# 8_Outputs_Card_with_I2C_schematic.net
KiCad netlist of a schematic drawn in EasyEDA
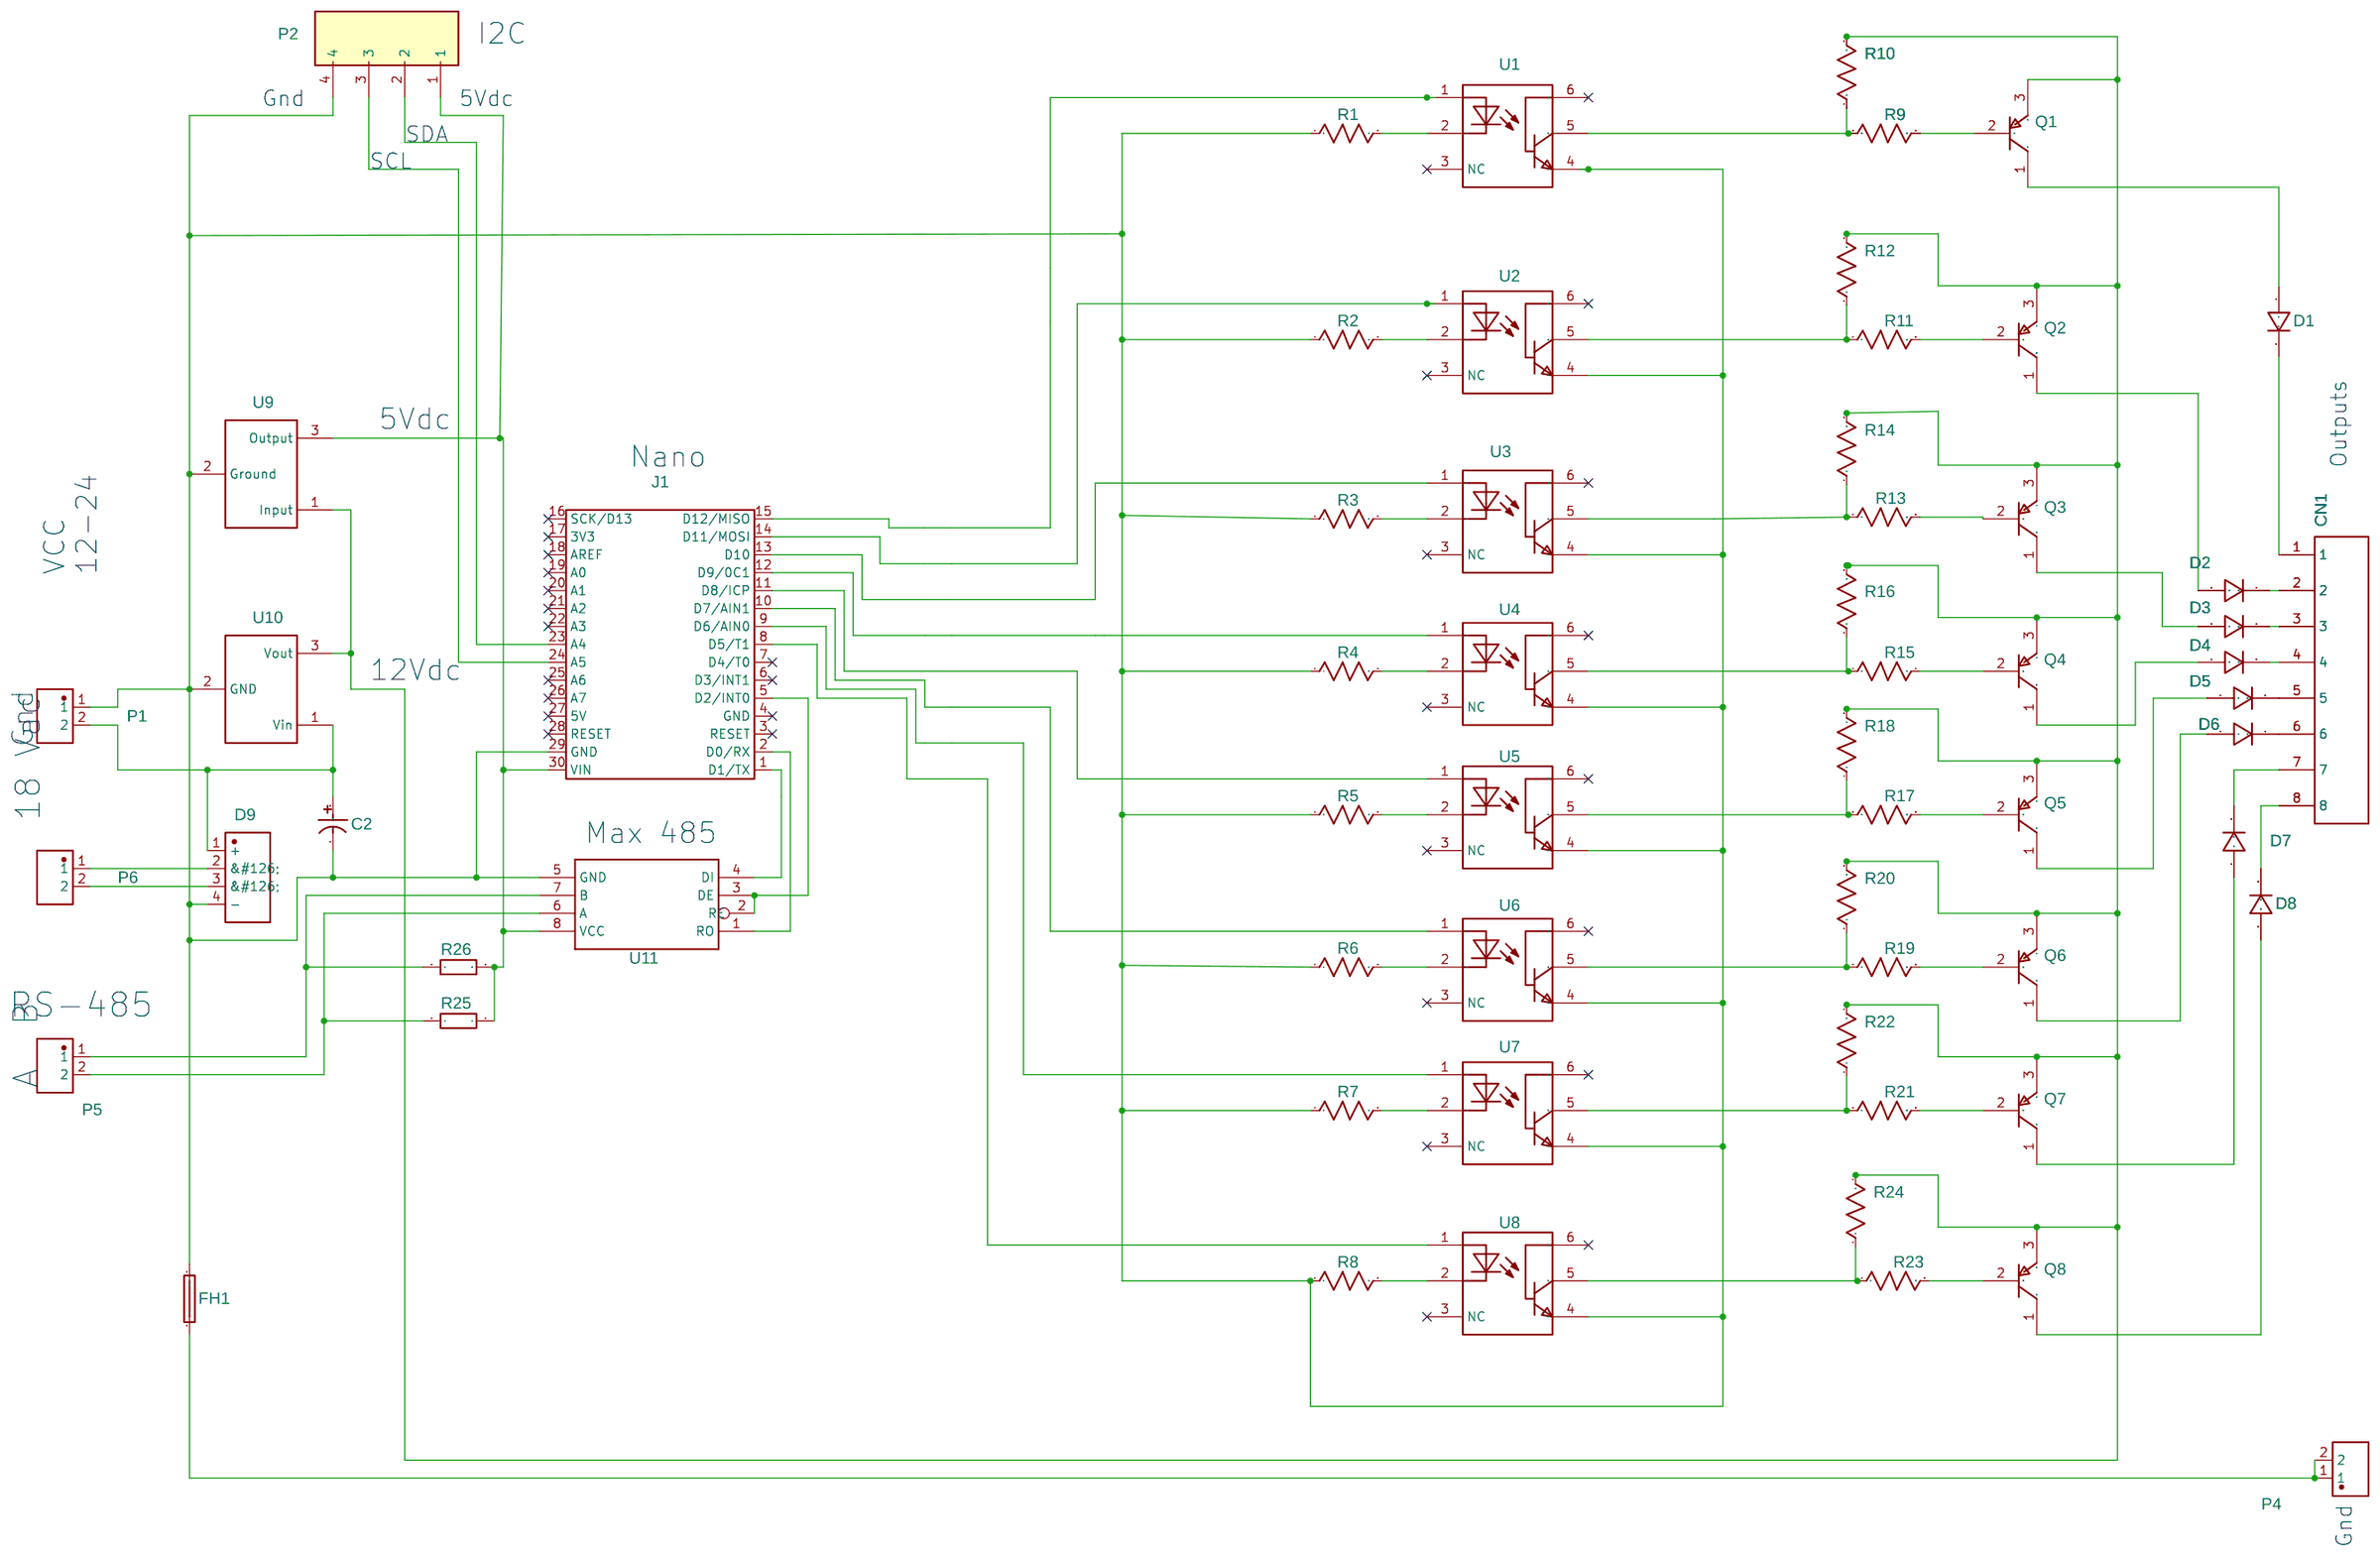
[diagram p0: schematic sheet]

(export (version "E")
  (design (tool "Eeschema 10.0.6"))
  (components
    (comp (ref "C2")
      (value "470uF")
      (fields
        (field (name "BOM_Manufacturer Part") "470uF 100V 16*25")
        (field (name "BOM_Supplier Part") "C72551")
      )
      (libsource (lib "") (part "470uF 100V 16*25"))
    )
    (comp (ref "CN1")
      (value "WJ25C-B-7.62-8P-13-00A")
      (fields (field (name "BOM_Supplier Part") "C49492"))
      (libsource (lib "") (part "Unknown_1530_395"))
    )
    (comp (ref "D1")
      (value "1N4001")
      (fields (field (name "BOM_Supplier Part") "C169150"))
      (libsource (lib "") (part "Unknown_1510_195"))
    )
    (comp (ref "D2")
      (value "1N4001")
      (fields (field (name "BOM_Supplier Part") "C169150"))
      (libsource (lib "") (part "Unknown_1485_345"))
    )
    (comp (ref "D3")
      (value "1N4001")
      (fields (field (name "BOM_Supplier Part") "C169150"))
      (libsource (lib "") (part "Unknown_1485_365"))
    )
    (comp (ref "D4")
      (value "1N4001")
      (fields (field (name "BOM_Supplier Part") "C169150"))
      (libsource (lib "") (part "Unknown_1485_385"))
    )
    (comp (ref "D5")
      (value "1N4001")
      (fields (field (name "BOM_Supplier Part") "C169150"))
      (libsource (lib "") (part "Unknown_1490_405"))
    )
    (comp (ref "D6")
      (value "1N4001")
      (fields (field (name "BOM_Supplier Part") "C169150"))
      (libsource (lib "") (part "Unknown_1490_425"))
    )
    (comp (ref "D7")
      (value "1N4001")
      (fields (field (name "BOM_Supplier Part") "C169150"))
      (libsource (lib "") (part "Unknown_1485_485"))
    )
    (comp (ref "D8")
      (value "1N4001")
      (fields (field (name "BOM_Supplier Part") "C169150"))
      (libsource (lib "") (part "Unknown_1500_520"))
    )
    (comp (ref "D9")
      (value "D50SB100")
      (fields (field (name "BOM_Supplier Part") "C411148"))
      (libsource (lib "") (part "Unknown_370_505"))
    )
    (comp (ref "FH1")
      (value "64600001003")
      (fields (field (name "BOM_Supplier Part") "C206887"))
      (libsource (lib "") (part "Unknown_345_740"))
    )
    (comp (ref "J1") (value "Arduino_Nano_Header") (libsource (lib "") (part "Unknown_605_375")))
    (comp (ref "P1")
      (value "WJ25C-B-2P")
      (fields (field (name "BOM_Supplier Part") "C8422"))
      (libsource (lib "") (part "Unknown_270_415"))
    )
    (comp (ref "P2")
      (value "WJ25C-B-4P")
      (fields (field (name "BOM_Supplier Part") "C8424"))
      (libsource (lib "") (part "WJ25C-B-4P"))
    )
    (comp (ref "P4")
      (value "WJ25C-B-2P")
      (fields (field (name "BOM_Supplier Part") "C8422"))
      (libsource (lib "") (part "Unknown_1550_835"))
    )
    (comp (ref "P5")
      (value "WJ25C-B-2P")
      (fields (field (name "BOM_Supplier Part") "C8422"))
      (libsource (lib "") (part "Unknown_270_610"))
    )
    (comp (ref "P6")
      (value "WJ25C-B-2P")
      (fields (field (name "BOM_Supplier Part") "C8422"))
      (libsource (lib "") (part "Unknown_270_505"))
    )
    (comp (ref "Q1")
      (value "2N4033")
      (fields (field (name "BOM_Supplier Part") "610-2N4033"))
      (libsource (lib "") (part "Unknown_1355_90"))
    )
    (comp (ref "Q2")
      (value "2N4033")
      (fields (field (name "BOM_Supplier Part") "610-2N4033"))
      (libsource (lib "") (part "Unknown_1360_205"))
    )
    (comp (ref "Q3")
      (value "2N4033")
      (fields (field (name "BOM_Supplier Part") "610-2N4033"))
      (libsource (lib "") (part "Unknown_1360_305"))
    )
    (comp (ref "Q4")
      (value "2N4033")
      (fields (field (name "BOM_Supplier Part") "610-2N4033"))
      (libsource (lib "") (part "Unknown_1360_390"))
    )
    (comp (ref "Q5")
      (value "2N4033")
      (fields (field (name "BOM_Supplier Part") "610-2N4033"))
      (libsource (lib "") (part "Unknown_1360_470"))
    )
    (comp (ref "Q6")
      (value "2N4033")
      (fields (field (name "BOM_Supplier Part") "610-2N4033"))
      (libsource (lib "") (part "Unknown_1360_555"))
    )
    (comp (ref "Q7")
      (value "2N4033")
      (fields (field (name "BOM_Supplier Part") "610-2N4033"))
      (libsource (lib "") (part "Unknown_1360_635"))
    )
    (comp (ref "Q8")
      (value "2N4033")
      (fields (field (name "BOM_Supplier Part") "610-2N4033"))
      (libsource (lib "") (part "Unknown_1360_730"))
    )
    (comp (ref "R1")
      (value "1k")
      (fields
        (field (name "BOM_Manufacturer Part") "MFR0W4F1001A50")
        (field (name "BOM_Supplier Part") "C57435")
      )
      (libsource (lib "") (part "Res_AXIAL-0.3(1/8W)_US"))
    )
    (comp (ref "R2")
      (value "1k")
      (fields
        (field (name "BOM_Manufacturer Part") "MFR0W4F1001A50")
        (field (name "BOM_Supplier Part") "C57435")
      )
      (libsource (lib "") (part "Res_AXIAL-0.3(1/8W)_US"))
    )
    (comp (ref "R3")
      (value "1k")
      (fields
        (field (name "BOM_Manufacturer Part") "MFR0W4F1001A50")
        (field (name "BOM_Supplier Part") "C57435")
      )
      (libsource (lib "") (part "Res_AXIAL-0.3(1/8W)_US"))
    )
    (comp (ref "R4")
      (value "1k")
      (fields
        (field (name "BOM_Manufacturer Part") "MFR0W4F1001A50")
        (field (name "BOM_Supplier Part") "C57435")
      )
      (libsource (lib "") (part "Res_AXIAL-0.3(1/8W)_US"))
    )
    (comp (ref "R5")
      (value "1k")
      (fields
        (field (name "BOM_Manufacturer Part") "MFR0W4F1001A50")
        (field (name "BOM_Supplier Part") "C57435")
      )
      (libsource (lib "") (part "Res_AXIAL-0.3(1/8W)_US"))
    )
    (comp (ref "R6")
      (value "1k")
      (fields
        (field (name "BOM_Manufacturer Part") "MFR0W4F1001A50")
        (field (name "BOM_Supplier Part") "C57435")
      )
      (libsource (lib "") (part "Res_AXIAL-0.3(1/8W)_US"))
    )
    (comp (ref "R7")
      (value "1k")
      (fields
        (field (name "BOM_Manufacturer Part") "MFR0W4F1001A50")
        (field (name "BOM_Supplier Part") "C57435")
      )
      (libsource (lib "") (part "Res_AXIAL-0.3(1/8W)_US"))
    )
    (comp (ref "R8")
      (value "1k")
      (fields
        (field (name "BOM_Manufacturer Part") "MFR0W4F1001A50")
        (field (name "BOM_Supplier Part") "C57435")
      )
      (libsource (lib "") (part "Res_AXIAL-0.3(1/8W)_US"))
    )
    (comp (ref "R9")
      (value "1k")
      (fields
        (field (name "BOM_Manufacturer Part") "MFR0W4F1001A50")
        (field (name "BOM_Supplier Part") "C57435")
      )
      (libsource (lib "") (part "Res_AXIAL-0.3(1/8W)_US"))
    )
    (comp (ref "R10")
      (value "1k")
      (fields
        (field (name "BOM_Manufacturer Part") "MFR0W4F1001A50")
        (field (name "BOM_Supplier Part") "C57435")
      )
      (libsource (lib "") (part "Res_AXIAL-0.3(1/8W)_US_1"))
    )
    (comp (ref "R11")
      (value "1k")
      (fields
        (field (name "BOM_Manufacturer Part") "MFR0W4F1001A50")
        (field (name "BOM_Supplier Part") "C57435")
      )
      (libsource (lib "") (part "Res_AXIAL-0.3(1/8W)_US"))
    )
    (comp (ref "R12")
      (value "1k")
      (fields
        (field (name "BOM_Manufacturer Part") "MFR0W4F1001A50")
        (field (name "BOM_Supplier Part") "C57435")
      )
      (libsource (lib "") (part "Res_AXIAL-0.3(1/8W)_US_1"))
    )
    (comp (ref "R13")
      (value "1k")
      (fields
        (field (name "BOM_Manufacturer Part") "MFR0W4F1001A50")
        (field (name "BOM_Supplier Part") "C57435")
      )
      (libsource (lib "") (part "Res_AXIAL-0.3(1/8W)_US"))
    )
    (comp (ref "R14")
      (value "1k")
      (fields
        (field (name "BOM_Manufacturer Part") "MFR0W4F1001A50")
        (field (name "BOM_Supplier Part") "C57435")
      )
      (libsource (lib "") (part "Res_AXIAL-0.3(1/8W)_US_1"))
    )
    (comp (ref "R15")
      (value "1k")
      (fields
        (field (name "BOM_Manufacturer Part") "MFR0W4F1001A50")
        (field (name "BOM_Supplier Part") "C57435")
      )
      (libsource (lib "") (part "Res_AXIAL-0.3(1/8W)_US"))
    )
    (comp (ref "R16")
      (value "1k")
      (fields
        (field (name "BOM_Manufacturer Part") "MFR0W4F1001A50")
        (field (name "BOM_Supplier Part") "C57435")
      )
      (libsource (lib "") (part "Res_AXIAL-0.3(1/8W)_US_1"))
    )
    (comp (ref "R17")
      (value "1k")
      (fields
        (field (name "BOM_Manufacturer Part") "MFR0W4F1001A50")
        (field (name "BOM_Supplier Part") "C57435")
      )
      (libsource (lib "") (part "Res_AXIAL-0.3(1/8W)_US"))
    )
    (comp (ref "R18")
      (value "1k")
      (fields
        (field (name "BOM_Manufacturer Part") "MFR0W4F1001A50")
        (field (name "BOM_Supplier Part") "C57435")
      )
      (libsource (lib "") (part "Res_AXIAL-0.3(1/8W)_US_1"))
    )
    (comp (ref "R19")
      (value "1k")
      (fields
        (field (name "BOM_Manufacturer Part") "MFR0W4F1001A50")
        (field (name "BOM_Supplier Part") "C57435")
      )
      (libsource (lib "") (part "Res_AXIAL-0.3(1/8W)_US"))
    )
    (comp (ref "R20")
      (value "1k")
      (fields
        (field (name "BOM_Manufacturer Part") "MFR0W4F1001A50")
        (field (name "BOM_Supplier Part") "C57435")
      )
      (libsource (lib "") (part "Res_AXIAL-0.3(1/8W)_US_1"))
    )
    (comp (ref "R21")
      (value "1k")
      (fields
        (field (name "BOM_Manufacturer Part") "MFR0W4F1001A50")
        (field (name "BOM_Supplier Part") "C57435")
      )
      (libsource (lib "") (part "Res_AXIAL-0.3(1/8W)_US"))
    )
    (comp (ref "R22")
      (value "1k")
      (fields
        (field (name "BOM_Manufacturer Part") "MFR0W4F1001A50")
        (field (name "BOM_Supplier Part") "C57435")
      )
      (libsource (lib "") (part "Res_AXIAL-0.3(1/8W)_US_1"))
    )
    (comp (ref "R23")
      (value "1k")
      (fields
        (field (name "BOM_Manufacturer Part") "MFR0W4F1001A50")
        (field (name "BOM_Supplier Part") "C57435")
      )
      (libsource (lib "") (part "Res_AXIAL-0.3(1/8W)_US"))
    )
    (comp (ref "R24")
      (value "1k")
      (fields
        (field (name "BOM_Manufacturer Part") "MFR0W4F1001A50")
        (field (name "BOM_Supplier Part") "C57435")
      )
      (libsource (lib "") (part "Res_AXIAL-0.3(1/8W)_US_1"))
    )
    (comp (ref "R25")
      (value "10K")
      (fields
        (field (name "BOM_Manufacturer Part") "CFR0W4J0103A50")
        (field (name "BOM_Supplier Part") "C61299")
      )
      (libsource (lib "") (part "CFR0W4J0103A50"))
    )
    (comp (ref "R26")
      (value "10K")
      (fields
        (field (name "BOM_Manufacturer Part") "CFR0W4J0103A50")
        (field (name "BOM_Supplier Part") "C61299")
      )
      (libsource (lib "") (part "CFR0W4J0103A50"))
    )
    (comp (ref "U1")
      (value "4N25M")
      (fields (field (name "BOM_Supplier Part") "C5241"))
      (libsource (lib "") (part "Unknown_1080_90"))
    )
    (comp (ref "U2")
      (value "4N25M")
      (fields (field (name "BOM_Supplier Part") "C5241"))
      (libsource (lib "") (part "Unknown_1080_205"))
    )
    (comp (ref "U3")
      (value "4N25M")
      (fields (field (name "BOM_Supplier Part") "C5241"))
      (libsource (lib "") (part "Unknown_1080_305"))
    )
    (comp (ref "U4")
      (value "4N25M")
      (fields (field (name "BOM_Supplier Part") "C5241"))
      (libsource (lib "") (part "Unknown_1080_390"))
    )
    (comp (ref "U5")
      (value "4N25M")
      (fields (field (name "BOM_Supplier Part") "C5241"))
      (libsource (lib "") (part "Unknown_1080_470"))
    )
    (comp (ref "U6")
      (value "4N25M")
      (fields (field (name "BOM_Supplier Part") "C5241"))
      (libsource (lib "") (part "Unknown_1080_555"))
    )
    (comp (ref "U7")
      (value "4N25M")
      (fields (field (name "BOM_Supplier Part") "C5241"))
      (libsource (lib "") (part "Unknown_1080_635"))
    )
    (comp (ref "U8")
      (value "4N25M")
      (fields (field (name "BOM_Supplier Part") "C5241"))
      (libsource (lib "") (part "Unknown_1080_730"))
    )
    (comp (ref "U9")
      (value "MC7805BTG")
      (fields (field (name "BOM_Supplier Part") "C45385"))
      (libsource (lib "") (part "Unknown_385_280"))
    )
    (comp (ref "U10")
      (value "CJ7812")
      (fields (field (name "BOM_Supplier Part") "C77894"))
      (libsource (lib "") (part "Unknown_385_400"))
    )
    (comp (ref "U11") (value "MAX485DIL") (libsource (lib "") (part "Unknown_600_520")))
  )
  (nets
    (net (code "1") (name "Net-(CN1-Pad1)") (class "Default")
      (node (ref "CN1") (pin "1") (pinfunction "1_1") (pintype "input"))
      (node (ref "D1") (pin "2") (pinfunction "2_2") (pintype "unspecified"))
    )
    (net (code "2") (name "Net-(CN1-Pad2)") (class "Default")
      (node (ref "CN1") (pin "2") (pinfunction "2_2") (pintype "input"))
      (node (ref "D2") (pin "2") (pinfunction "2_2") (pintype "unspecified"))
    )
    (net (code "3") (name "Net-(CN1-Pad3)") (class "Default")
      (node (ref "CN1") (pin "3") (pinfunction "3_3") (pintype "input"))
      (node (ref "D3") (pin "2") (pinfunction "2_2") (pintype "unspecified"))
    )
    (net (code "4") (name "Net-(CN1-Pad4)") (class "Default")
      (node (ref "CN1") (pin "4") (pinfunction "4_4") (pintype "input"))
      (node (ref "D4") (pin "2") (pinfunction "2_2") (pintype "unspecified"))
    )
    (net (code "5") (name "Net-(CN1-Pad5)") (class "Default")
      (node (ref "CN1") (pin "5") (pinfunction "5_5") (pintype "input"))
      (node (ref "D5") (pin "2") (pinfunction "2_2") (pintype "unspecified"))
    )
    (net (code "6") (name "Net-(CN1-Pad6)") (class "Default")
      (node (ref "CN1") (pin "6") (pinfunction "6_6") (pintype "input"))
      (node (ref "D6") (pin "2") (pinfunction "2_2") (pintype "unspecified"))
    )
    (net (code "7") (name "Net-(CN1-Pad7)") (class "Default")
      (node (ref "CN1") (pin "7") (pinfunction "7_7") (pintype "input"))
      (node (ref "D7") (pin "2") (pinfunction "2_2") (pintype "unspecified"))
    )
    (net (code "8") (name "Net-(CN1-Pad8)") (class "Default")
      (node (ref "CN1") (pin "8") (pinfunction "8_8") (pintype "input"))
      (node (ref "D8") (pin "2") (pinfunction "2_2") (pintype "unspecified"))
    )
    (net (code "9") (name "Net-(D9-&#126;-Pad2)") (class "Default")
      (node (ref "D9") (pin "2") (pinfunction "&#126;_2") (pintype "unspecified"))
      (node (ref "P6") (pin "1") (pinfunction "1_1") (pintype "unspecified"))
    )
    (net (code "10") (name "Net-(D9-&#126;-Pad3)") (class "Default")
      (node (ref "D9") (pin "3") (pinfunction "&#126;_3") (pintype "unspecified"))
      (node (ref "P6") (pin "2") (pinfunction "2_2") (pintype "unspecified"))
    )
    (net (code "11") (name "Net-(D9-+)") (class "Default")
      (node (ref "C2") (pin "1") (pinfunction "1_1") (pintype "input"))
      (node (ref "D9") (pin "1") (pinfunction "+_1") (pintype "unspecified"))
      (node (ref "P1") (pin "2") (pinfunction "2_2") (pintype "unspecified"))
      (node (ref "U10") (pin "1") (pinfunction "Vin_1") (pintype "unspecified"))
    )
    (net (code "12") (name "Net-(D9--)") (class "Default")
      (node (ref "C2") (pin "2") (pinfunction "2_2") (pintype "input"))
      (node (ref "D9") (pin "4") (pinfunction "-_4") (pintype "unspecified"))
      (node (ref "FH1") (pin "2") (pinfunction "2_2") (pintype "unspecified"))
      (node (ref "J1") (pin "29") (pinfunction "GND_29") (pintype "unspecified"))
      (node (ref "P1") (pin "1") (pinfunction "1_1") (pintype "unspecified"))
      (node (ref "P2") (pin "4") (pinfunction "4_4") (pintype "input"))
      (node (ref "R1") (pin "1") (pinfunction "1_1") (pintype "unspecified"))
      (node (ref "R2") (pin "1") (pinfunction "1_1") (pintype "unspecified"))
      (node (ref "R3") (pin "1") (pinfunction "1_1") (pintype "unspecified"))
      (node (ref "R4") (pin "1") (pinfunction "1_1") (pintype "unspecified"))
      (node (ref "R5") (pin "1") (pinfunction "1_1") (pintype "unspecified"))
      (node (ref "R6") (pin "1") (pinfunction "1_1") (pintype "unspecified"))
      (node (ref "R7") (pin "1") (pinfunction "1_1") (pintype "unspecified"))
      (node (ref "R8") (pin "1") (pinfunction "1_1") (pintype "unspecified"))
      (node (ref "U1") (pin "4") (pinfunction "4_4") (pintype "unspecified"))
      (node (ref "U10") (pin "2") (pinfunction "GND_2") (pintype "unspecified"))
      (node (ref "U11") (pin "5") (pinfunction "GND_5") (pintype "unspecified"))
      (node (ref "U2") (pin "4") (pinfunction "4_4") (pintype "unspecified"))
      (node (ref "U3") (pin "4") (pinfunction "4_4") (pintype "unspecified"))
      (node (ref "U4") (pin "4") (pinfunction "4_4") (pintype "unspecified"))
      (node (ref "U5") (pin "4") (pinfunction "4_4") (pintype "unspecified"))
      (node (ref "U6") (pin "4") (pinfunction "4_4") (pintype "unspecified"))
      (node (ref "U7") (pin "4") (pinfunction "4_4") (pintype "unspecified"))
      (node (ref "U8") (pin "4") (pinfunction "4_4") (pintype "unspecified"))
      (node (ref "U9") (pin "2") (pinfunction "Ground_2") (pintype "unspecified"))
    )
    (net (code "13") (name "Net-(FH1-Pad1)") (class "Default")
      (node (ref "FH1") (pin "1") (pinfunction "1_1") (pintype "unspecified"))
      (node (ref "P4") (pin "1") (pinfunction "1_1") (pintype "unspecified"))
      (node (ref "P4") (pin "2") (pinfunction "2_2") (pintype "unspecified"))
    )
    (net (code "14") (name "Net-(J1-A4)") (class "Default")
      (node (ref "J1") (pin "23") (pinfunction "A4_23") (pintype "unspecified"))
      (node (ref "P2") (pin "2") (pinfunction "2_2") (pintype "input"))
    )
    (net (code "15") (name "Net-(J1-A5)") (class "Default")
      (node (ref "J1") (pin "24") (pinfunction "A5_24") (pintype "unspecified"))
      (node (ref "P2") (pin "3") (pinfunction "3_3") (pintype "input"))
    )
    (net (code "16") (name "Net-(J1-D0{slash}RX)") (class "Default")
      (node (ref "J1") (pin "2") (pinfunction "D0/RX_2") (pintype "unspecified"))
      (node (ref "U11") (pin "1") (pinfunction "RO_1") (pintype "unspecified"))
    )
    (net (code "17") (name "Net-(J1-D1{slash}TX)") (class "Default")
      (node (ref "J1") (pin "1") (pinfunction "D1/TX_1") (pintype "unspecified"))
      (node (ref "U11") (pin "4") (pinfunction "DI_4") (pintype "unspecified"))
    )
    (net (code "18") (name "Net-(J1-D2{slash}INT0)") (class "Default")
      (node (ref "J1") (pin "5") (pinfunction "D2/INT0_5") (pintype "unspecified"))
      (node (ref "U11") (pin "2") (pinfunction "RE_2") (pintype "unspecified"))
      (node (ref "U11") (pin "3") (pinfunction "DE_3") (pintype "unspecified"))
    )
    (net (code "19") (name "Net-(J1-D5{slash}T1)") (class "Default")
      (node (ref "J1") (pin "8") (pinfunction "D5/T1_8") (pintype "unspecified"))
      (node (ref "U8") (pin "1") (pinfunction "1_1") (pintype "unspecified"))
    )
    (net (code "20") (name "Net-(J1-D6{slash}AIN0)") (class "Default")
      (node (ref "J1") (pin "9") (pinfunction "D6/AIN0_9") (pintype "unspecified"))
      (node (ref "U7") (pin "1") (pinfunction "1_1") (pintype "unspecified"))
    )
    (net (code "21") (name "Net-(J1-D7{slash}AIN1)") (class "Default")
      (node (ref "J1") (pin "10") (pinfunction "D7/AIN1_10") (pintype "unspecified"))
      (node (ref "U6") (pin "1") (pinfunction "1_1") (pintype "unspecified"))
    )
    (net (code "22") (name "Net-(J1-D8{slash}ICP)") (class "Default")
      (node (ref "J1") (pin "11") (pinfunction "D8/ICP_11") (pintype "unspecified"))
      (node (ref "U5") (pin "1") (pinfunction "1_1") (pintype "unspecified"))
    )
    (net (code "23") (name "Net-(J1-D9{slash}0C1)") (class "Default")
      (node (ref "J1") (pin "12") (pinfunction "D9/0C1_12") (pintype "unspecified"))
      (node (ref "U4") (pin "1") (pinfunction "1_1") (pintype "unspecified"))
    )
    (net (code "24") (name "Net-(J1-D10)") (class "Default")
      (node (ref "J1") (pin "13") (pinfunction "D10_13") (pintype "unspecified"))
      (node (ref "U3") (pin "1") (pinfunction "1_1") (pintype "unspecified"))
    )
    (net (code "25") (name "Net-(J1-D11{slash}MOSI)") (class "Default")
      (node (ref "J1") (pin "14") (pinfunction "D11/MOSI_14") (pintype "unspecified"))
      (node (ref "U2") (pin "1") (pinfunction "1_1") (pintype "unspecified"))
    )
    (net (code "26") (name "Net-(J1-D12{slash}MISO)") (class "Default")
      (node (ref "J1") (pin "15") (pinfunction "D12/MISO_15") (pintype "unspecified"))
      (node (ref "U1") (pin "1") (pinfunction "1_1") (pintype "unspecified"))
    )
    (net (code "27") (name "Net-(J1-VIN)") (class "Default")
      (node (ref "J1") (pin "30") (pinfunction "VIN_30") (pintype "unspecified"))
      (node (ref "P2") (pin "1") (pinfunction "1_1") (pintype "input"))
      (node (ref "R25") (pin "2") (pinfunction "2_2") (pintype "input"))
      (node (ref "R26") (pin "2") (pinfunction "2_2") (pintype "input"))
      (node (ref "U11") (pin "8") (pinfunction "VCC_8") (pintype "unspecified"))
      (node (ref "U9") (pin "3") (pinfunction "Output_3") (pintype "unspecified"))
    )
    (net (code "28") (name "Net-(Q1-B)") (class "Default")
      (node (ref "Q1") (pin "2") (pinfunction "B_2") (pintype "unspecified"))
      (node (ref "R9") (pin "2") (pinfunction "2_2") (pintype "unspecified"))
    )
    (net (code "29") (name "Net-(Q1-C)") (class "Default")
      (node (ref "D1") (pin "1") (pinfunction "1_1") (pintype "unspecified"))
      (node (ref "Q1") (pin "1") (pinfunction "C_1") (pintype "unspecified"))
    )
    (net (code "30") (name "Net-(Q1-E)") (class "Default")
      (node (ref "Q1") (pin "3") (pinfunction "E_3") (pintype "unspecified"))
      (node (ref "Q2") (pin "3") (pinfunction "E_3") (pintype "unspecified"))
      (node (ref "Q3") (pin "3") (pinfunction "E_3") (pintype "unspecified"))
      (node (ref "Q4") (pin "3") (pinfunction "E_3") (pintype "unspecified"))
      (node (ref "Q5") (pin "3") (pinfunction "E_3") (pintype "unspecified"))
      (node (ref "Q6") (pin "3") (pinfunction "E_3") (pintype "unspecified"))
      (node (ref "Q7") (pin "3") (pinfunction "E_3") (pintype "unspecified"))
      (node (ref "Q8") (pin "3") (pinfunction "E_3") (pintype "unspecified"))
      (node (ref "R10") (pin "2") (pinfunction "2_2") (pintype "unspecified"))
      (node (ref "R12") (pin "2") (pinfunction "2_2") (pintype "unspecified"))
      (node (ref "R14") (pin "2") (pinfunction "2_2") (pintype "unspecified"))
      (node (ref "R16") (pin "2") (pinfunction "2_2") (pintype "unspecified"))
      (node (ref "R18") (pin "2") (pinfunction "2_2") (pintype "unspecified"))
      (node (ref "R20") (pin "2") (pinfunction "2_2") (pintype "unspecified"))
      (node (ref "R22") (pin "2") (pinfunction "2_2") (pintype "unspecified"))
      (node (ref "R24") (pin "2") (pinfunction "2_2") (pintype "unspecified"))
      (node (ref "U10") (pin "3") (pinfunction "Vout_3") (pintype "unspecified"))
      (node (ref "U9") (pin "1") (pinfunction "Input_1") (pintype "unspecified"))
    )
    (net (code "31") (name "Net-(Q2-B)") (class "Default")
      (node (ref "Q2") (pin "2") (pinfunction "B_2") (pintype "unspecified"))
      (node (ref "R11") (pin "2") (pinfunction "2_2") (pintype "unspecified"))
    )
    (net (code "32") (name "Net-(Q2-C)") (class "Default")
      (node (ref "D2") (pin "1") (pinfunction "1_1") (pintype "unspecified"))
      (node (ref "Q2") (pin "1") (pinfunction "C_1") (pintype "unspecified"))
    )
    (net (code "33") (name "Net-(Q3-B)") (class "Default")
      (node (ref "Q3") (pin "2") (pinfunction "B_2") (pintype "unspecified"))
      (node (ref "R13") (pin "2") (pinfunction "2_2") (pintype "unspecified"))
    )
    (net (code "34") (name "Net-(Q3-C)") (class "Default")
      (node (ref "D3") (pin "1") (pinfunction "1_1") (pintype "unspecified"))
      (node (ref "Q3") (pin "1") (pinfunction "C_1") (pintype "unspecified"))
    )
    (net (code "35") (name "Net-(Q4-B)") (class "Default")
      (node (ref "Q4") (pin "2") (pinfunction "B_2") (pintype "unspecified"))
      (node (ref "R15") (pin "2") (pinfunction "2_2") (pintype "unspecified"))
    )
    (net (code "36") (name "Net-(Q4-C)") (class "Default")
      (node (ref "D4") (pin "1") (pinfunction "1_1") (pintype "unspecified"))
      (node (ref "Q4") (pin "1") (pinfunction "C_1") (pintype "unspecified"))
    )
    (net (code "37") (name "Net-(Q5-B)") (class "Default")
      (node (ref "Q5") (pin "2") (pinfunction "B_2") (pintype "unspecified"))
      (node (ref "R17") (pin "2") (pinfunction "2_2") (pintype "unspecified"))
    )
    (net (code "38") (name "Net-(Q5-C)") (class "Default")
      (node (ref "D5") (pin "1") (pinfunction "1_1") (pintype "unspecified"))
      (node (ref "Q5") (pin "1") (pinfunction "C_1") (pintype "unspecified"))
    )
    (net (code "39") (name "Net-(Q6-B)") (class "Default")
      (node (ref "Q6") (pin "2") (pinfunction "B_2") (pintype "unspecified"))
      (node (ref "R19") (pin "2") (pinfunction "2_2") (pintype "unspecified"))
    )
    (net (code "40") (name "Net-(Q6-C)") (class "Default")
      (node (ref "D6") (pin "1") (pinfunction "1_1") (pintype "unspecified"))
      (node (ref "Q6") (pin "1") (pinfunction "C_1") (pintype "unspecified"))
    )
    (net (code "41") (name "Net-(Q7-B)") (class "Default")
      (node (ref "Q7") (pin "2") (pinfunction "B_2") (pintype "unspecified"))
      (node (ref "R21") (pin "2") (pinfunction "2_2") (pintype "unspecified"))
    )
    (net (code "42") (name "Net-(Q7-C)") (class "Default")
      (node (ref "D7") (pin "1") (pinfunction "1_1") (pintype "unspecified"))
      (node (ref "Q7") (pin "1") (pinfunction "C_1") (pintype "unspecified"))
    )
    (net (code "43") (name "Net-(Q8-B)") (class "Default")
      (node (ref "Q8") (pin "2") (pinfunction "B_2") (pintype "unspecified"))
      (node (ref "R23") (pin "2") (pinfunction "2_2") (pintype "unspecified"))
    )
    (net (code "44") (name "Net-(Q8-C)") (class "Default")
      (node (ref "D8") (pin "1") (pinfunction "1_1") (pintype "unspecified"))
      (node (ref "Q8") (pin "1") (pinfunction "C_1") (pintype "unspecified"))
    )
    (net (code "45") (name "Net-(R1-Pad2)") (class "Default")
      (node (ref "R1") (pin "2") (pinfunction "2_2") (pintype "unspecified"))
      (node (ref "U1") (pin "2") (pinfunction "2_2") (pintype "unspecified"))
    )
    (net (code "46") (name "Net-(R2-Pad2)") (class "Default")
      (node (ref "R2") (pin "2") (pinfunction "2_2") (pintype "unspecified"))
      (node (ref "U2") (pin "2") (pinfunction "2_2") (pintype "unspecified"))
    )
    (net (code "47") (name "Net-(R3-Pad2)") (class "Default")
      (node (ref "R3") (pin "2") (pinfunction "2_2") (pintype "unspecified"))
      (node (ref "U3") (pin "2") (pinfunction "2_2") (pintype "unspecified"))
    )
    (net (code "48") (name "Net-(R4-Pad2)") (class "Default")
      (node (ref "R4") (pin "2") (pinfunction "2_2") (pintype "unspecified"))
      (node (ref "U4") (pin "2") (pinfunction "2_2") (pintype "unspecified"))
    )
    (net (code "49") (name "Net-(R5-Pad2)") (class "Default")
      (node (ref "R5") (pin "2") (pinfunction "2_2") (pintype "unspecified"))
      (node (ref "U5") (pin "2") (pinfunction "2_2") (pintype "unspecified"))
    )
    (net (code "50") (name "Net-(R6-Pad2)") (class "Default")
      (node (ref "R6") (pin "2") (pinfunction "2_2") (pintype "unspecified"))
      (node (ref "U6") (pin "2") (pinfunction "2_2") (pintype "unspecified"))
    )
    (net (code "51") (name "Net-(R7-Pad2)") (class "Default")
      (node (ref "R7") (pin "2") (pinfunction "2_2") (pintype "unspecified"))
      (node (ref "U7") (pin "2") (pinfunction "2_2") (pintype "unspecified"))
    )
    (net (code "52") (name "Net-(R8-Pad2)") (class "Default")
      (node (ref "R8") (pin "2") (pinfunction "2_2") (pintype "unspecified"))
      (node (ref "U8") (pin "2") (pinfunction "2_2") (pintype "unspecified"))
    )
    (net (code "53") (name "Net-(R10-Pad1)") (class "Default")
      (node (ref "R10") (pin "1") (pinfunction "1_1") (pintype "unspecified"))
      (node (ref "R9") (pin "1") (pinfunction "1_1") (pintype "unspecified"))
      (node (ref "U1") (pin "5") (pinfunction "5_5") (pintype "unspecified"))
    )
    (net (code "54") (name "Net-(R11-Pad1)") (class "Default")
      (node (ref "R11") (pin "1") (pinfunction "1_1") (pintype "unspecified"))
      (node (ref "R12") (pin "1") (pinfunction "1_1") (pintype "unspecified"))
      (node (ref "U2") (pin "5") (pinfunction "5_5") (pintype "unspecified"))
    )
    (net (code "55") (name "Net-(R13-Pad1)") (class "Default")
      (node (ref "R13") (pin "1") (pinfunction "1_1") (pintype "unspecified"))
      (node (ref "R14") (pin "1") (pinfunction "1_1") (pintype "unspecified"))
      (node (ref "U3") (pin "5") (pinfunction "5_5") (pintype "unspecified"))
    )
    (net (code "56") (name "Net-(R15-Pad1)") (class "Default")
      (node (ref "R15") (pin "1") (pinfunction "1_1") (pintype "unspecified"))
      (node (ref "R16") (pin "1") (pinfunction "1_1") (pintype "unspecified"))
      (node (ref "U4") (pin "5") (pinfunction "5_5") (pintype "unspecified"))
    )
    (net (code "57") (name "Net-(R17-Pad1)") (class "Default")
      (node (ref "R17") (pin "1") (pinfunction "1_1") (pintype "unspecified"))
      (node (ref "R18") (pin "1") (pinfunction "1_1") (pintype "unspecified"))
      (node (ref "U5") (pin "5") (pinfunction "5_5") (pintype "unspecified"))
    )
    (net (code "58") (name "Net-(R19-Pad1)") (class "Default")
      (node (ref "R19") (pin "1") (pinfunction "1_1") (pintype "unspecified"))
      (node (ref "R20") (pin "1") (pinfunction "1_1") (pintype "unspecified"))
      (node (ref "U6") (pin "5") (pinfunction "5_5") (pintype "unspecified"))
    )
    (net (code "59") (name "Net-(R21-Pad1)") (class "Default")
      (node (ref "R21") (pin "1") (pinfunction "1_1") (pintype "unspecified"))
      (node (ref "R22") (pin "1") (pinfunction "1_1") (pintype "unspecified"))
      (node (ref "U7") (pin "5") (pinfunction "5_5") (pintype "unspecified"))
    )
    (net (code "60") (name "Net-(R23-Pad1)") (class "Default")
      (node (ref "R23") (pin "1") (pinfunction "1_1") (pintype "unspecified"))
      (node (ref "R24") (pin "1") (pinfunction "1_1") (pintype "unspecified"))
      (node (ref "U8") (pin "5") (pinfunction "5_5") (pintype "unspecified"))
    )
    (net (code "61") (name "Net-(U11-A)") (class "Default")
      (node (ref "P5") (pin "2") (pinfunction "2_2") (pintype "unspecified"))
      (node (ref "R25") (pin "1") (pinfunction "1_1") (pintype "input"))
      (node (ref "U11") (pin "6") (pinfunction "A_6") (pintype "unspecified"))
    )
    (net (code "62") (name "Net-(U11-B)") (class "Default")
      (node (ref "P5") (pin "1") (pinfunction "1_1") (pintype "unspecified"))
      (node (ref "R26") (pin "1") (pinfunction "1_1") (pintype "input"))
      (node (ref "U11") (pin "7") (pinfunction "B_7") (pintype "unspecified"))
    )
    (net (code "63") (name "unconnected-(J1-3V3-Pad17)") (class "Default")
      (node (ref "J1") (pin "17") (pinfunction "3V3_17") (pintype "unspecified+no_connect"))
    )
    (net (code "64") (name "unconnected-(J1-5V-Pad27)") (class "Default")
      (node (ref "J1") (pin "27") (pinfunction "5V_27") (pintype "unspecified+no_connect"))
    )
    (net (code "65") (name "unconnected-(J1-A0-Pad19)") (class "Default")
      (node (ref "J1") (pin "19") (pinfunction "A0_19") (pintype "unspecified+no_connect"))
    )
    (net (code "66") (name "unconnected-(J1-A1-Pad20)") (class "Default")
      (node (ref "J1") (pin "20") (pinfunction "A1_20") (pintype "unspecified+no_connect"))
    )
    (net (code "67") (name "unconnected-(J1-A2-Pad21)") (class "Default")
      (node (ref "J1") (pin "21") (pinfunction "A2_21") (pintype "unspecified+no_connect"))
    )
    (net (code "68") (name "unconnected-(J1-A3-Pad22)") (class "Default")
      (node (ref "J1") (pin "22") (pinfunction "A3_22") (pintype "unspecified+no_connect"))
    )
    (net (code "69") (name "unconnected-(J1-A6-Pad25)") (class "Default")
      (node (ref "J1") (pin "25") (pinfunction "A6_25") (pintype "unspecified+no_connect"))
    )
    (net (code "70") (name "unconnected-(J1-A7-Pad26)") (class "Default")
      (node (ref "J1") (pin "26") (pinfunction "A7_26") (pintype "unspecified+no_connect"))
    )
    (net (code "71") (name "unconnected-(J1-AREF-Pad18)") (class "Default")
      (node (ref "J1") (pin "18") (pinfunction "AREF_18") (pintype "unspecified+no_connect"))
    )
    (net (code "72") (name "unconnected-(J1-D3{slash}INT1-Pad6)") (class "Default")
      (node (ref "J1") (pin "6") (pinfunction "D3/INT1_6") (pintype "unspecified+no_connect"))
    )
    (net (code "73") (name "unconnected-(J1-D4{slash}T0-Pad7)") (class "Default")
      (node (ref "J1") (pin "7") (pinfunction "D4/T0_7") (pintype "unspecified+no_connect"))
    )
    (net (code "74") (name "unconnected-(J1-GND-Pad4)") (class "Default")
      (node (ref "J1") (pin "4") (pinfunction "GND_4") (pintype "unspecified+no_connect"))
    )
    (net (code "75") (name "unconnected-(J1-RESET-Pad3)") (class "Default")
      (node (ref "J1") (pin "3") (pinfunction "RESET_3") (pintype "unspecified+no_connect"))
    )
    (net (code "76") (name "unconnected-(J1-RESET-Pad28)") (class "Default")
      (node (ref "J1") (pin "28") (pinfunction "RESET_28") (pintype "unspecified+no_connect"))
    )
    (net (code "77") (name "unconnected-(J1-SCK{slash}D13-Pad16)") (class "Default")
      (node (ref "J1") (pin "16") (pinfunction "SCK/D13_16") (pintype "unspecified+no_connect"))
    )
    (net (code "78") (name "unconnected-(U1-NC-Pad3)") (class "Default")
      (node (ref "U1") (pin "3") (pinfunction "NC_3") (pintype "unspecified+no_connect"))
    )
    (net (code "79") (name "unconnected-(U1-Pad6)") (class "Default")
      (node (ref "U1") (pin "6") (pinfunction "6_6") (pintype "unspecified+no_connect"))
    )
    (net (code "80") (name "unconnected-(U2-NC-Pad3)") (class "Default")
      (node (ref "U2") (pin "3") (pinfunction "NC_3") (pintype "unspecified+no_connect"))
    )
    (net (code "81") (name "unconnected-(U2-Pad6)") (class "Default")
      (node (ref "U2") (pin "6") (pinfunction "6_6") (pintype "unspecified+no_connect"))
    )
    (net (code "82") (name "unconnected-(U3-NC-Pad3)") (class "Default")
      (node (ref "U3") (pin "3") (pinfunction "NC_3") (pintype "unspecified+no_connect"))
    )
    (net (code "83") (name "unconnected-(U3-Pad6)") (class "Default")
      (node (ref "U3") (pin "6") (pinfunction "6_6") (pintype "unspecified+no_connect"))
    )
    (net (code "84") (name "unconnected-(U4-NC-Pad3)") (class "Default")
      (node (ref "U4") (pin "3") (pinfunction "NC_3") (pintype "unspecified+no_connect"))
    )
    (net (code "85") (name "unconnected-(U4-Pad6)") (class "Default")
      (node (ref "U4") (pin "6") (pinfunction "6_6") (pintype "unspecified+no_connect"))
    )
    (net (code "86") (name "unconnected-(U5-NC-Pad3)") (class "Default")
      (node (ref "U5") (pin "3") (pinfunction "NC_3") (pintype "unspecified+no_connect"))
    )
    (net (code "87") (name "unconnected-(U5-Pad6)") (class "Default")
      (node (ref "U5") (pin "6") (pinfunction "6_6") (pintype "unspecified+no_connect"))
    )
    (net (code "88") (name "unconnected-(U6-NC-Pad3)") (class "Default")
      (node (ref "U6") (pin "3") (pinfunction "NC_3") (pintype "unspecified+no_connect"))
    )
    (net (code "89") (name "unconnected-(U6-Pad6)") (class "Default")
      (node (ref "U6") (pin "6") (pinfunction "6_6") (pintype "unspecified+no_connect"))
    )
    (net (code "90") (name "unconnected-(U7-NC-Pad3)") (class "Default")
      (node (ref "U7") (pin "3") (pinfunction "NC_3") (pintype "unspecified+no_connect"))
    )
    (net (code "91") (name "unconnected-(U7-Pad6)") (class "Default")
      (node (ref "U7") (pin "6") (pinfunction "6_6") (pintype "unspecified+no_connect"))
    )
    (net (code "92") (name "unconnected-(U8-NC-Pad3)") (class "Default")
      (node (ref "U8") (pin "3") (pinfunction "NC_3") (pintype "unspecified+no_connect"))
    )
    (net (code "93") (name "unconnected-(U8-Pad6)") (class "Default")
      (node (ref "U8") (pin "6") (pinfunction "6_6") (pintype "unspecified+no_connect"))
    )
  )
)
